# IMX6ULL_CORE_sch7.net
KiCad netlist of a schematic drawn in Altium Designer
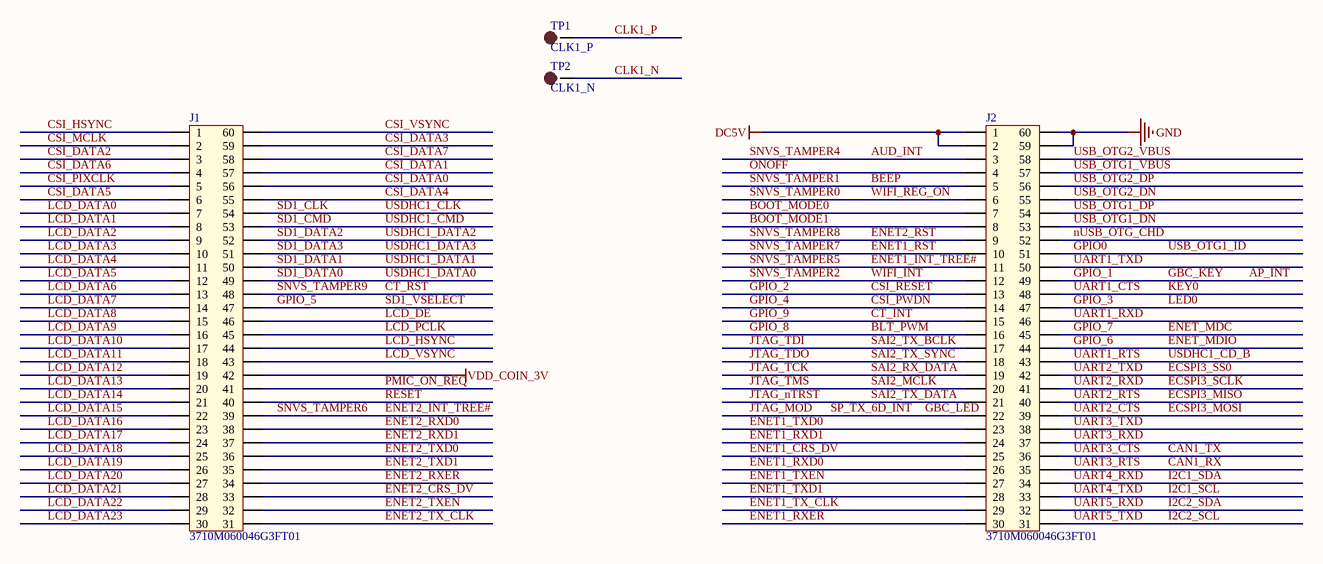
[diagram p0: IMX6ULL_CORE_sch7.SchDoc]

(export (version "E")
  (design (tool "Eeschema 10.0.6"))
  (components
    (comp (ref "J1")
      (value "3710M060046G3FT01")
      (footprint "3710F060046G3FT01")
      (description "3710F060046G3FT01")
      (libsource (lib "linux_coreSCHLIB") (part "3710F"))
    )
    (comp (ref "J2")
      (value "3710M060046G3FT01")
      (footprint "3710F060046G3FT01")
      (description "3710F060046G3FT01")
      (libsource (lib "linux_coreSCHLIB") (part "3710F"))
    )
    (comp (ref "TP1")
      (value "CLK1_P")
      (footprint "TP-1.0")
      (description "测试点")
      (libsource (lib "linux_coreSCHLIB") (part "TEST-POINT"))
    )
    (comp (ref "TP2")
      (value "CLK1_N")
      (footprint "TP-1.0")
      (description "测试点")
      (libsource (lib "linux_coreSCHLIB") (part "TEST-POINT"))
    )
  )
  (nets
    (net (code "1") (name "/AP_INT") (class "Default")
      (node (ref "J2") (pin "49") (pinfunction "49_49") (pintype "passive"))
    )
    (net (code "2") (name "/AUD_INT") (class "Default")
      (node (ref "J2") (pin "3") (pinfunction "3_3") (pintype "passive"))
    )
    (net (code "3") (name "/BEEP") (class "Default")
      (node (ref "J2") (pin "5") (pinfunction "5_5") (pintype "passive"))
    )
    (net (code "4") (name "/BLT_PWM") (class "Default")
      (node (ref "J2") (pin "16") (pinfunction "16_16") (pintype "passive"))
    )
    (net (code "5") (name "/BOOT_MODE0") (class "Default")
      (node (ref "J2") (pin "7") (pinfunction "7_7") (pintype "passive"))
    )
    (net (code "6") (name "/BOOT_MODE1") (class "Default")
      (node (ref "J2") (pin "8") (pinfunction "8_8") (pintype "passive"))
    )
    (net (code "7") (name "/CAN1_RX") (class "Default")
      (node (ref "J2") (pin "35") (pinfunction "35_35") (pintype "passive"))
    )
    (net (code "8") (name "/CAN1_TX") (class "Default")
      (node (ref "J2") (pin "36") (pinfunction "36_36") (pintype "passive"))
    )
    (net (code "9") (name "/CLK1_N") (class "Default")
      (node (ref "TP2") (pin "1") (pinfunction "1_1") (pintype "passive"))
    )
    (net (code "10") (name "/CLK1_P") (class "Default")
      (node (ref "TP1") (pin "1") (pinfunction "1_1") (pintype "passive"))
    )
    (net (code "11") (name "/CSI_DATA0") (class "Default")
      (node (ref "J1") (pin "56") (pinfunction "56_56") (pintype "passive"))
    )
    (net (code "12") (name "/CSI_DATA1") (class "Default")
      (node (ref "J1") (pin "57") (pinfunction "57_57") (pintype "passive"))
    )
    (net (code "13") (name "/CSI_DATA2") (class "Default")
      (node (ref "J1") (pin "3") (pinfunction "3_3") (pintype "passive"))
    )
    (net (code "14") (name "/CSI_DATA3") (class "Default")
      (node (ref "J1") (pin "59") (pinfunction "59_59") (pintype "passive"))
    )
    (net (code "15") (name "/CSI_DATA4") (class "Default")
      (node (ref "J1") (pin "55") (pinfunction "55_55") (pintype "passive"))
    )
    (net (code "16") (name "/CSI_DATA5") (class "Default")
      (node (ref "J1") (pin "6") (pinfunction "6_6") (pintype "passive"))
    )
    (net (code "17") (name "/CSI_DATA6") (class "Default")
      (node (ref "J1") (pin "4") (pinfunction "4_4") (pintype "passive"))
    )
    (net (code "18") (name "/CSI_DATA7") (class "Default")
      (node (ref "J1") (pin "58") (pinfunction "58_58") (pintype "passive"))
    )
    (net (code "19") (name "/CSI_HSYNC") (class "Default")
      (node (ref "J1") (pin "1") (pinfunction "1_1") (pintype "passive"))
    )
    (net (code "20") (name "/CSI_MCLK") (class "Default")
      (node (ref "J1") (pin "2") (pinfunction "2_2") (pintype "passive"))
    )
    (net (code "21") (name "/CSI_PIXCLK") (class "Default")
      (node (ref "J1") (pin "5") (pinfunction "5_5") (pintype "passive"))
    )
    (net (code "22") (name "/CSI_PWDN") (class "Default")
      (node (ref "J2") (pin "14") (pinfunction "14_14") (pintype "passive"))
    )
    (net (code "23") (name "/CSI_RESET") (class "Default")
      (node (ref "J2") (pin "13") (pinfunction "13_13") (pintype "passive"))
    )
    (net (code "24") (name "/CSI_VSYNC") (class "Default")
      (node (ref "J1") (pin "60") (pinfunction "60_60") (pintype "passive"))
    )
    (net (code "25") (name "/CT_INT") (class "Default")
      (node (ref "J2") (pin "15") (pinfunction "15_15") (pintype "passive"))
    )
    (net (code "26") (name "/CT_RST") (class "Default")
      (node (ref "J1") (pin "48") (pinfunction "48_48") (pintype "passive"))
    )
    (net (code "27") (name "/ECSPI3_MISO") (class "Default")
      (node (ref "J2") (pin "40") (pinfunction "40_40") (pintype "passive"))
    )
    (net (code "28") (name "/ECSPI3_MOSI") (class "Default")
      (node (ref "J2") (pin "39") (pinfunction "39_39") (pintype "passive"))
    )
    (net (code "29") (name "/ECSPI3_SCLK") (class "Default")
      (node (ref "J2") (pin "41") (pinfunction "41_41") (pintype "passive"))
    )
    (net (code "30") (name "/ECSPI3_SS0") (class "Default")
      (node (ref "J2") (pin "42") (pinfunction "42_42") (pintype "passive"))
    )
    (net (code "31") (name "/ENET1_CRS_DV") (class "Default")
      (node (ref "J2") (pin "25") (pinfunction "25_25") (pintype "passive"))
    )
    (net (code "32") (name "/ENET1_INT_TREE#") (class "Default")
      (node (ref "J2") (pin "11") (pinfunction "11_11") (pintype "passive"))
    )
    (net (code "33") (name "/ENET1_RST") (class "Default")
      (node (ref "J2") (pin "10") (pinfunction "10_10") (pintype "passive"))
    )
    (net (code "34") (name "/ENET1_RXD0") (class "Default")
      (node (ref "J2") (pin "26") (pinfunction "26_26") (pintype "passive"))
    )
    (net (code "35") (name "/ENET1_RXD1") (class "Default")
      (node (ref "J2") (pin "24") (pinfunction "24_24") (pintype "passive"))
    )
    (net (code "36") (name "/ENET1_RXER") (class "Default")
      (node (ref "J2") (pin "30") (pinfunction "30_30") (pintype "passive"))
    )
    (net (code "37") (name "/ENET1_TXD0") (class "Default")
      (node (ref "J2") (pin "23") (pinfunction "23_23") (pintype "passive"))
    )
    (net (code "38") (name "/ENET1_TXD1") (class "Default")
      (node (ref "J2") (pin "28") (pinfunction "28_28") (pintype "passive"))
    )
    (net (code "39") (name "/ENET1_TXEN") (class "Default")
      (node (ref "J2") (pin "27") (pinfunction "27_27") (pintype "passive"))
    )
    (net (code "40") (name "/ENET1_TX_CLK") (class "Default")
      (node (ref "J2") (pin "29") (pinfunction "29_29") (pintype "passive"))
    )
    (net (code "41") (name "/ENET2_CRS_DV") (class "Default")
      (node (ref "J1") (pin "33") (pinfunction "33_33") (pintype "passive"))
    )
    (net (code "42") (name "/ENET2_INT_TREE#") (class "Default")
      (node (ref "J1") (pin "39") (pinfunction "39_39") (pintype "passive"))
    )
    (net (code "43") (name "/ENET2_RST") (class "Default")
      (node (ref "J2") (pin "9") (pinfunction "9_9") (pintype "passive"))
    )
    (net (code "44") (name "/ENET2_RXD0") (class "Default")
      (node (ref "J1") (pin "38") (pinfunction "38_38") (pintype "passive"))
    )
    (net (code "45") (name "/ENET2_RXD1") (class "Default")
      (node (ref "J1") (pin "37") (pinfunction "37_37") (pintype "passive"))
    )
    (net (code "46") (name "/ENET2_RXER") (class "Default")
      (node (ref "J1") (pin "34") (pinfunction "34_34") (pintype "passive"))
    )
    (net (code "47") (name "/ENET2_TXD0") (class "Default")
      (node (ref "J1") (pin "36") (pinfunction "36_36") (pintype "passive"))
    )
    (net (code "48") (name "/ENET2_TXD1") (class "Default")
      (node (ref "J1") (pin "35") (pinfunction "35_35") (pintype "passive"))
    )
    (net (code "49") (name "/ENET2_TXEN") (class "Default")
      (node (ref "J1") (pin "32") (pinfunction "32_32") (pintype "passive"))
    )
    (net (code "50") (name "/ENET2_TX_CLK") (class "Default")
      (node (ref "J1") (pin "31") (pinfunction "31_31") (pintype "passive"))
    )
    (net (code "51") (name "/ENET_MDC") (class "Default")
      (node (ref "J2") (pin "45") (pinfunction "45_45") (pintype "passive"))
    )
    (net (code "52") (name "/ENET_MDIO") (class "Default")
      (node (ref "J2") (pin "44") (pinfunction "44_44") (pintype "passive"))
    )
    (net (code "53") (name "/GBC_LED") (class "Default")
      (node (ref "J2") (pin "22") (pinfunction "22_22") (pintype "passive"))
    )
    (net (code "54") (name "/GPIO0") (class "Default")
      (node (ref "J2") (pin "51") (pinfunction "51_51") (pintype "passive"))
    )
    (net (code "55") (name "/GPIO_3") (class "Default")
      (node (ref "J2") (pin "47") (pinfunction "47_47") (pintype "passive"))
    )
    (net (code "56") (name "/GPIO_5") (class "Default")
      (node (ref "J1") (pin "47") (pinfunction "47_47") (pintype "passive"))
    )
    (net (code "57") (name "/I2C1_SCL") (class "Default")
      (node (ref "J2") (pin "33") (pinfunction "33_33") (pintype "passive"))
    )
    (net (code "58") (name "/I2C1_SDA") (class "Default")
      (node (ref "J2") (pin "34") (pinfunction "34_34") (pintype "passive"))
    )
    (net (code "59") (name "/I2C2_SCL") (class "Default")
      (node (ref "J2") (pin "31") (pinfunction "31_31") (pintype "passive"))
    )
    (net (code "60") (name "/I2C2_SDA") (class "Default")
      (node (ref "J2") (pin "32") (pinfunction "32_32") (pintype "passive"))
    )
    (net (code "61") (name "/JTAG_TCK") (class "Default")
      (node (ref "J2") (pin "19") (pinfunction "19_19") (pintype "passive"))
    )
    (net (code "62") (name "/JTAG_TDI") (class "Default")
      (node (ref "J2") (pin "17") (pinfunction "17_17") (pintype "passive"))
    )
    (net (code "63") (name "/JTAG_TDO") (class "Default")
      (node (ref "J2") (pin "18") (pinfunction "18_18") (pintype "passive"))
    )
    (net (code "64") (name "/JTAG_TMS") (class "Default")
      (node (ref "J2") (pin "20") (pinfunction "20_20") (pintype "passive"))
    )
    (net (code "65") (name "/JTAG_nTRST") (class "Default")
      (node (ref "J2") (pin "21") (pinfunction "21_21") (pintype "passive"))
    )
    (net (code "66") (name "/KEY0") (class "Default")
      (node (ref "J2") (pin "48") (pinfunction "48_48") (pintype "passive"))
    )
    (net (code "67") (name "/LCD_DATA0") (class "Default")
      (node (ref "J1") (pin "7") (pinfunction "7_7") (pintype "passive"))
    )
    (net (code "68") (name "/LCD_DATA1") (class "Default")
      (node (ref "J1") (pin "8") (pinfunction "8_8") (pintype "passive"))
    )
    (net (code "69") (name "/LCD_DATA2") (class "Default")
      (node (ref "J1") (pin "9") (pinfunction "9_9") (pintype "passive"))
    )
    (net (code "70") (name "/LCD_DATA3") (class "Default")
      (node (ref "J1") (pin "10") (pinfunction "10_10") (pintype "passive"))
    )
    (net (code "71") (name "/LCD_DATA4") (class "Default")
      (node (ref "J1") (pin "11") (pinfunction "11_11") (pintype "passive"))
    )
    (net (code "72") (name "/LCD_DATA5") (class "Default")
      (node (ref "J1") (pin "12") (pinfunction "12_12") (pintype "passive"))
    )
    (net (code "73") (name "/LCD_DATA6") (class "Default")
      (node (ref "J1") (pin "13") (pinfunction "13_13") (pintype "passive"))
    )
    (net (code "74") (name "/LCD_DATA7") (class "Default")
      (node (ref "J1") (pin "14") (pinfunction "14_14") (pintype "passive"))
    )
    (net (code "75") (name "/LCD_DATA8") (class "Default")
      (node (ref "J1") (pin "15") (pinfunction "15_15") (pintype "passive"))
    )
    (net (code "76") (name "/LCD_DATA9") (class "Default")
      (node (ref "J1") (pin "16") (pinfunction "16_16") (pintype "passive"))
    )
    (net (code "77") (name "/LCD_DATA10") (class "Default")
      (node (ref "J1") (pin "17") (pinfunction "17_17") (pintype "passive"))
    )
    (net (code "78") (name "/LCD_DATA11") (class "Default")
      (node (ref "J1") (pin "18") (pinfunction "18_18") (pintype "passive"))
    )
    (net (code "79") (name "/LCD_DATA12") (class "Default")
      (node (ref "J1") (pin "19") (pinfunction "19_19") (pintype "passive"))
    )
    (net (code "80") (name "/LCD_DATA13") (class "Default")
      (node (ref "J1") (pin "20") (pinfunction "20_20") (pintype "passive"))
    )
    (net (code "81") (name "/LCD_DATA14") (class "Default")
      (node (ref "J1") (pin "21") (pinfunction "21_21") (pintype "passive"))
    )
    (net (code "82") (name "/LCD_DATA15") (class "Default")
      (node (ref "J1") (pin "22") (pinfunction "22_22") (pintype "passive"))
    )
    (net (code "83") (name "/LCD_DATA16") (class "Default")
      (node (ref "J1") (pin "23") (pinfunction "23_23") (pintype "passive"))
    )
    (net (code "84") (name "/LCD_DATA17") (class "Default")
      (node (ref "J1") (pin "24") (pinfunction "24_24") (pintype "passive"))
    )
    (net (code "85") (name "/LCD_DATA18") (class "Default")
      (node (ref "J1") (pin "25") (pinfunction "25_25") (pintype "passive"))
    )
    (net (code "86") (name "/LCD_DATA19") (class "Default")
      (node (ref "J1") (pin "26") (pinfunction "26_26") (pintype "passive"))
    )
    (net (code "87") (name "/LCD_DATA20") (class "Default")
      (node (ref "J1") (pin "27") (pinfunction "27_27") (pintype "passive"))
    )
    (net (code "88") (name "/LCD_DATA21") (class "Default")
      (node (ref "J1") (pin "28") (pinfunction "28_28") (pintype "passive"))
    )
    (net (code "89") (name "/LCD_DATA22") (class "Default")
      (node (ref "J1") (pin "29") (pinfunction "29_29") (pintype "passive"))
    )
    (net (code "90") (name "/LCD_DATA23") (class "Default")
      (node (ref "J1") (pin "30") (pinfunction "30_30") (pintype "passive"))
    )
    (net (code "91") (name "/LCD_DE") (class "Default")
      (node (ref "J1") (pin "46") (pinfunction "46_46") (pintype "passive"))
    )
    (net (code "92") (name "/LCD_HSYNC") (class "Default")
      (node (ref "J1") (pin "44") (pinfunction "44_44") (pintype "passive"))
    )
    (net (code "93") (name "/LCD_PCLK") (class "Default")
      (node (ref "J1") (pin "45") (pinfunction "45_45") (pintype "passive"))
    )
    (net (code "94") (name "/LCD_VSYNC") (class "Default")
      (node (ref "J1") (pin "43") (pinfunction "43_43") (pintype "passive"))
    )
    (net (code "95") (name "/ONOFF") (class "Default")
      (node (ref "J2") (pin "4") (pinfunction "4_4") (pintype "passive"))
    )
    (net (code "96") (name "/PMIC_ON_REQ") (class "Default")
      (node (ref "J1") (pin "41") (pinfunction "41_41") (pintype "passive"))
    )
    (net (code "97") (name "/RESET") (class "Default")
      (node (ref "J1") (pin "40") (pinfunction "40_40") (pintype "passive"))
    )
    (net (code "98") (name "/SD1_CLK") (class "Default")
      (node (ref "J1") (pin "54") (pinfunction "54_54") (pintype "passive"))
    )
    (net (code "99") (name "/SD1_CMD") (class "Default")
      (node (ref "J1") (pin "53") (pinfunction "53_53") (pintype "passive"))
    )
    (net (code "100") (name "/SD1_DATA0") (class "Default")
      (node (ref "J1") (pin "49") (pinfunction "49_49") (pintype "passive"))
    )
    (net (code "101") (name "/SD1_DATA1") (class "Default")
      (node (ref "J1") (pin "50") (pinfunction "50_50") (pintype "passive"))
    )
    (net (code "102") (name "/SD1_DATA2") (class "Default")
      (node (ref "J1") (pin "52") (pinfunction "52_52") (pintype "passive"))
    )
    (net (code "103") (name "/SD1_DATA3") (class "Default")
      (node (ref "J1") (pin "51") (pinfunction "51_51") (pintype "passive"))
    )
    (net (code "104") (name "/SNVS_TAMPER0") (class "Default")
      (node (ref "J2") (pin "6") (pinfunction "6_6") (pintype "passive"))
    )
    (net (code "105") (name "/SNVS_TAMPER2") (class "Default")
      (node (ref "J2") (pin "12") (pinfunction "12_12") (pintype "passive"))
    )
    (net (code "106") (name "/UART1_RTS") (class "Default")
      (node (ref "J2") (pin "43") (pinfunction "43_43") (pintype "passive"))
    )
    (net (code "107") (name "/UART1_RXD") (class "Default")
      (node (ref "J2") (pin "46") (pinfunction "46_46") (pintype "passive"))
    )
    (net (code "108") (name "/UART1_TXD") (class "Default")
      (node (ref "J2") (pin "50") (pinfunction "50_50") (pintype "passive"))
    )
    (net (code "109") (name "/UART3_RXD") (class "Default")
      (node (ref "J2") (pin "37") (pinfunction "37_37") (pintype "passive"))
    )
    (net (code "110") (name "/UART3_TXD") (class "Default")
      (node (ref "J2") (pin "38") (pinfunction "38_38") (pintype "passive"))
    )
    (net (code "111") (name "/USB_OTG1_DN") (class "Default")
      (node (ref "J2") (pin "53") (pinfunction "53_53") (pintype "passive"))
    )
    (net (code "112") (name "/USB_OTG1_DP") (class "Default")
      (node (ref "J2") (pin "54") (pinfunction "54_54") (pintype "passive"))
    )
    (net (code "113") (name "/USB_OTG1_VBUS") (class "Default")
      (node (ref "J2") (pin "57") (pinfunction "57_57") (pintype "passive"))
    )
    (net (code "114") (name "/USB_OTG2_DN") (class "Default")
      (node (ref "J2") (pin "55") (pinfunction "55_55") (pintype "passive"))
    )
    (net (code "115") (name "/USB_OTG2_DP") (class "Default")
      (node (ref "J2") (pin "56") (pinfunction "56_56") (pintype "passive"))
    )
    (net (code "116") (name "/USB_OTG2_VBUS") (class "Default")
      (node (ref "J2") (pin "58") (pinfunction "58_58") (pintype "passive"))
    )
    (net (code "117") (name "/nUSB_OTG_CHD") (class "Default")
      (node (ref "J2") (pin "52") (pinfunction "52_52") (pintype "passive"))
    )
    (net (code "118") (name "DC5V") (class "Default")
      (node (ref "J2") (pin "1") (pinfunction "1_1") (pintype "passive"))
      (node (ref "J2") (pin "2") (pinfunction "2_2") (pintype "passive"))
    )
    (net (code "119") (name "GND") (class "Default")
      (node (ref "J2") (pin "59") (pinfunction "59_59") (pintype "passive"))
      (node (ref "J2") (pin "60") (pinfunction "60_60") (pintype "passive"))
    )
    (net (code "120") (name "VDD_COIN_3V") (class "Default")
      (node (ref "J1") (pin "42") (pinfunction "42_42") (pintype "passive"))
    )
  )
)
